# FPGA_0.net
KiCad netlist of a schematic drawn in Altium Designer
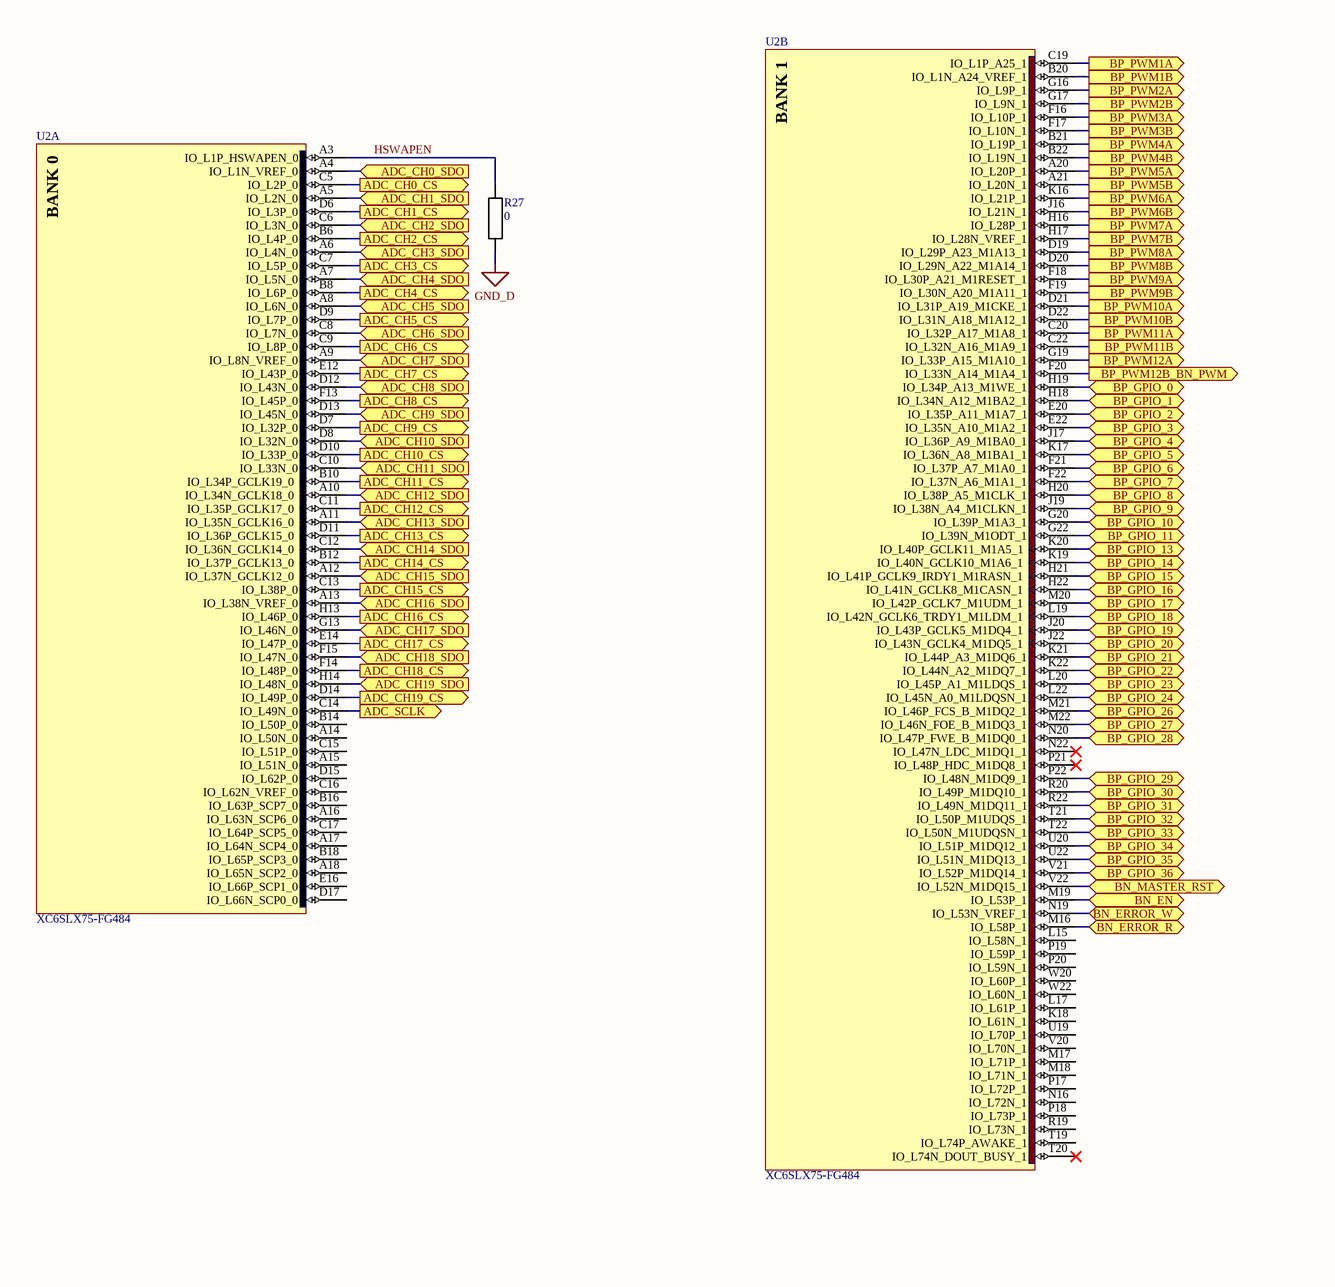
[diagram p0: FPGA_0.SchDoc, left]
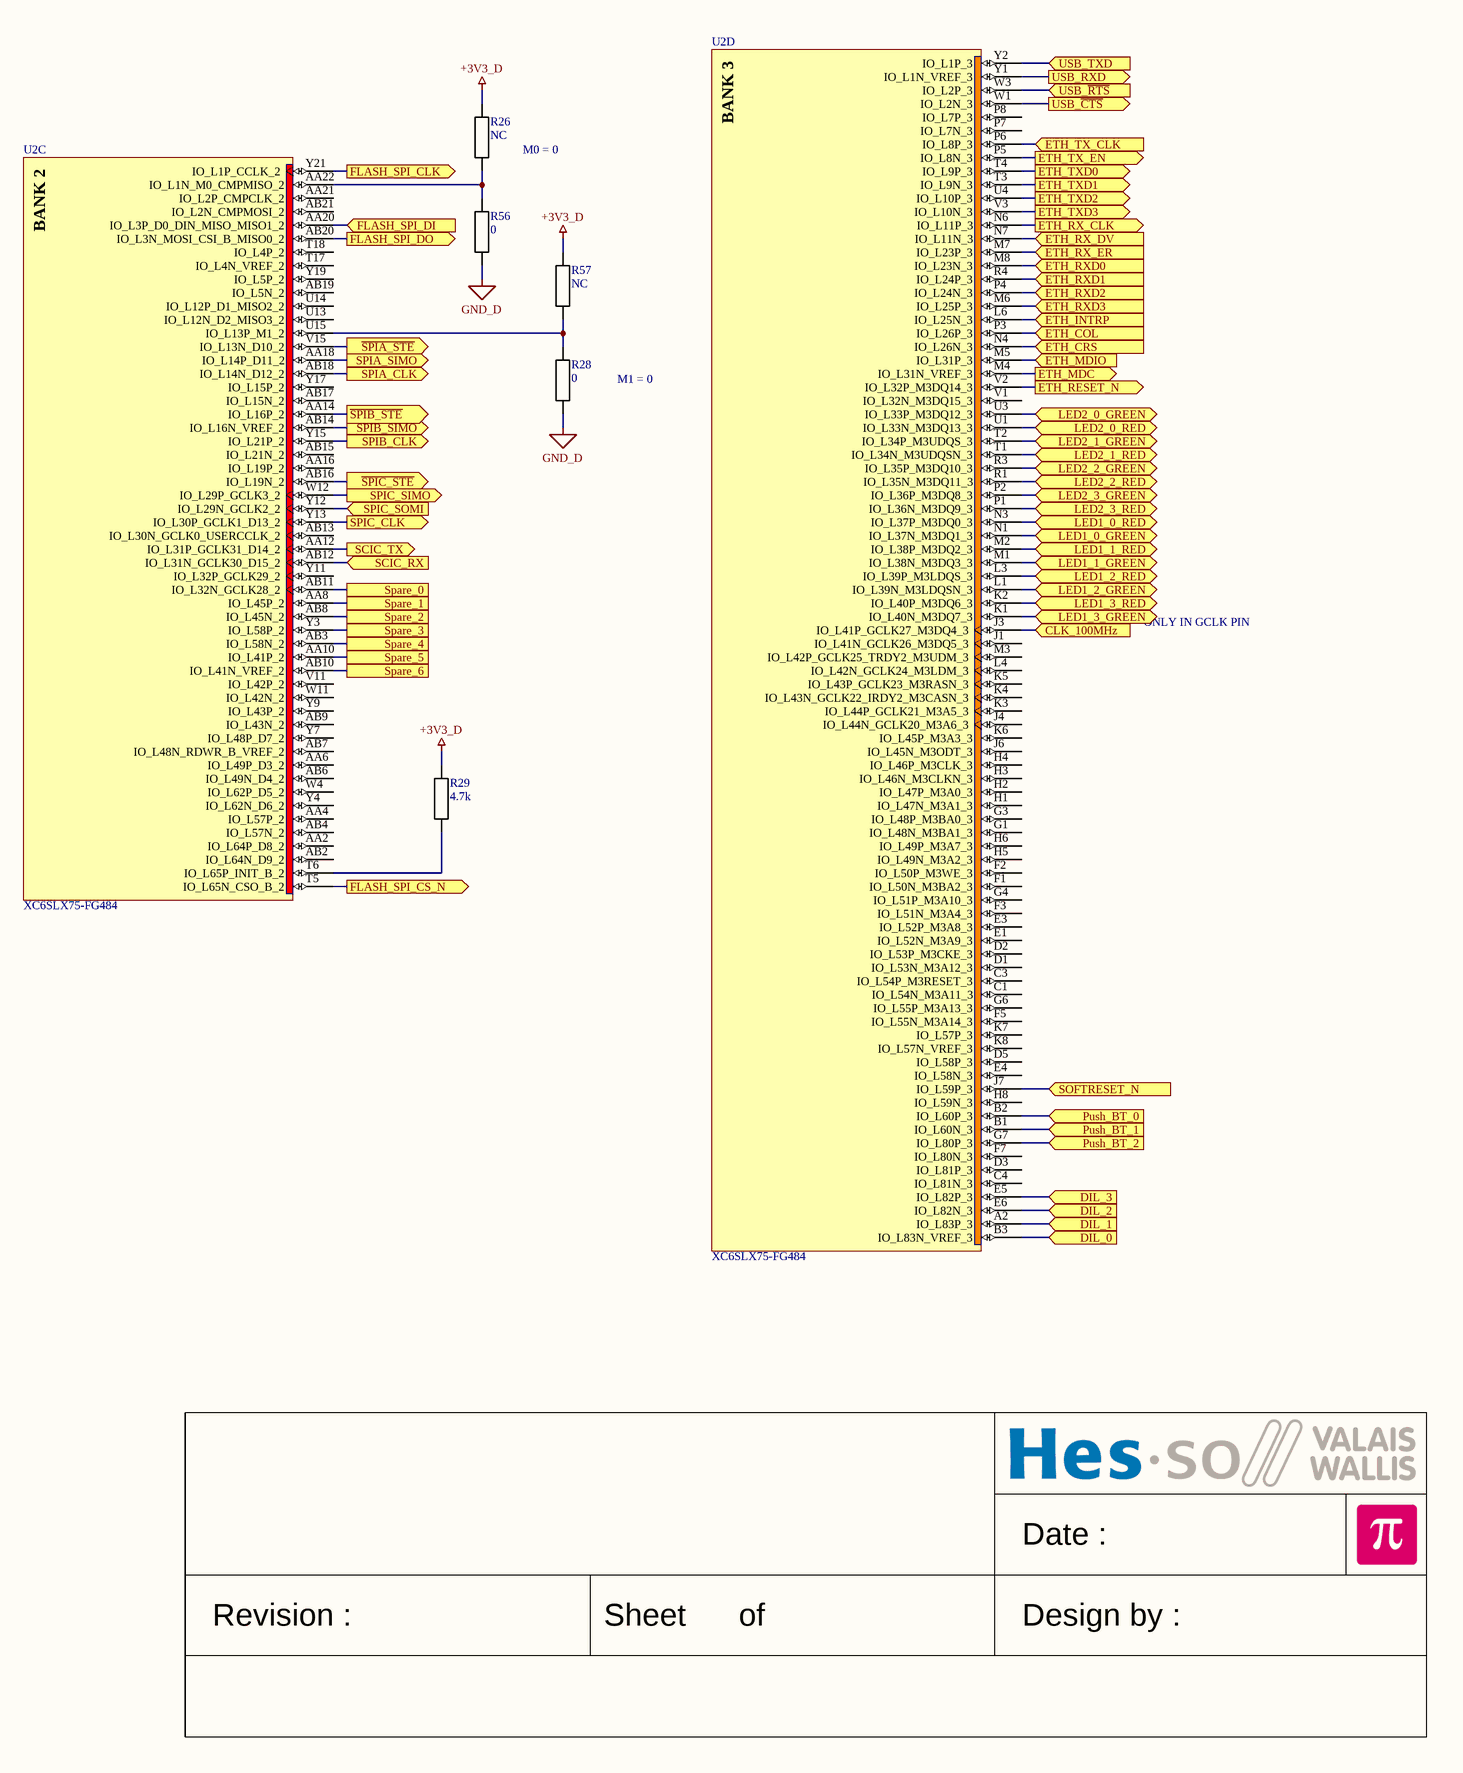
[diagram p1: FPGA_0.SchDoc, right]

(export (version "E")
  (design (tool "Eeschema 10.0.6"))
  (components
    (comp (ref "R26")
      (value "NC")
      (footprint "RESISTOR 2012 REFLOW")
      (description "Resistor 1% 50V 125mW 2012(0805)")
      (libsource (lib "Resistor") (part "Resistor"))
    )
    (comp (ref "R27")
      (value "0")
      (footprint "RESISTOR 2012 REFLOW")
      (description "Resistor 1% 50V 125mW 2012(0805)")
      (libsource (lib "Resistor") (part "Resistor"))
    )
    (comp (ref "R28")
      (value "0")
      (footprint "RESISTOR 2012 REFLOW")
      (description "Resistor 1% 50V 125mW 2012(0805)")
      (libsource (lib "Resistor") (part "Resistor"))
    )
    (comp (ref "R29")
      (value "4.7k")
      (footprint "RESISTOR 2012 REFLOW")
      (description "Resistor 1% 50V 125mW 2012(0805)")
      (libsource (lib "Resistor") (part "Resistor"))
    )
    (comp (ref "R56")
      (value "0")
      (footprint "RESISTOR 2012 REFLOW")
      (description "Resistor 1% 50V 125mW 2012(0805)")
      (libsource (lib "Resistor") (part "Resistor"))
    )
    (comp (ref "R57")
      (value "NC")
      (footprint "RESISTOR 2012 REFLOW")
      (description "Resistor 1% 50V 125mW 2012(0805)")
      (libsource (lib "Resistor") (part "Resistor"))
    )
    (comp (ref "U2")
      (value "XC6SLX75-FG484")
      (footprint "BGA484 P1.0 C23X23 H2.2")
      (description "Spartan-6 LXT 1.2V FPGA, 268 User I/Os, 484-Ball Fine-Pitch BGA (1.0mm Pitch)")
      (libsource (lib "Processor") (part "XC6SLX75-FG484"))
    )
  )
  (nets
    (net (code "1") (name "+3V3_D") (class "Default")
      (node (ref "R26") (pin "2") (pinfunction "2_2") (pintype "passive"))
      (node (ref "R29") (pin "2") (pinfunction "2_2") (pintype "passive"))
      (node (ref "R57") (pin "2") (pinfunction "2_2") (pintype "passive"))
    )
    (net (code "2") (name "/ADC_CH0_CS") (class "Default")
      (node (ref "U2") (pin "C5") (pinfunction "IO_L2P_0_C5") (pintype "bidirectional"))
    )
    (net (code "3") (name "/ADC_CH0_SDO") (class "Default")
      (node (ref "U2") (pin "A4") (pinfunction "IO_L1N_VREF_0_A4") (pintype "bidirectional"))
    )
    (net (code "4") (name "/ADC_CH1_CS") (class "Default")
      (node (ref "U2") (pin "D6") (pinfunction "IO_L3P_0_D6") (pintype "bidirectional"))
    )
    (net (code "5") (name "/ADC_CH1_SDO") (class "Default")
      (node (ref "U2") (pin "A5") (pinfunction "IO_L2N_0_A5") (pintype "bidirectional"))
    )
    (net (code "6") (name "/ADC_CH2_CS") (class "Default")
      (node (ref "U2") (pin "B6") (pinfunction "IO_L4P_0_B6") (pintype "bidirectional"))
    )
    (net (code "7") (name "/ADC_CH2_SDO") (class "Default")
      (node (ref "U2") (pin "C6") (pinfunction "IO_L3N_0_C6") (pintype "bidirectional"))
    )
    (net (code "8") (name "/ADC_CH3_CS") (class "Default")
      (node (ref "U2") (pin "C7") (pinfunction "IO_L5P_0_C7") (pintype "bidirectional"))
    )
    (net (code "9") (name "/ADC_CH3_SDO") (class "Default")
      (node (ref "U2") (pin "A6") (pinfunction "IO_L4N_0_A6") (pintype "bidirectional"))
    )
    (net (code "10") (name "/ADC_CH4_CS") (class "Default")
      (node (ref "U2") (pin "B8") (pinfunction "IO_L6P_0_B8") (pintype "bidirectional"))
    )
    (net (code "11") (name "/ADC_CH4_SDO") (class "Default")
      (node (ref "U2") (pin "A7") (pinfunction "IO_L5N_0_A7") (pintype "bidirectional"))
    )
    (net (code "12") (name "/ADC_CH5_CS") (class "Default")
      (node (ref "U2") (pin "D9") (pinfunction "IO_L7P_0_D9") (pintype "bidirectional"))
    )
    (net (code "13") (name "/ADC_CH5_SDO") (class "Default")
      (node (ref "U2") (pin "A8") (pinfunction "IO_L6N_0_A8") (pintype "bidirectional"))
    )
    (net (code "14") (name "/ADC_CH6_CS") (class "Default")
      (node (ref "U2") (pin "C9") (pinfunction "IO_L8P_0_C9") (pintype "bidirectional"))
    )
    (net (code "15") (name "/ADC_CH6_SDO") (class "Default")
      (node (ref "U2") (pin "C8") (pinfunction "IO_L7N_0_C8") (pintype "bidirectional"))
    )
    (net (code "16") (name "/ADC_CH7_CS") (class "Default")
      (node (ref "U2") (pin "E12") (pinfunction "IO_L43P_0_E12") (pintype "bidirectional"))
    )
    (net (code "17") (name "/ADC_CH7_SDO") (class "Default")
      (node (ref "U2") (pin "A9") (pinfunction "IO_L8N_VREF_0_A9") (pintype "bidirectional"))
    )
    (net (code "18") (name "/ADC_CH8_CS") (class "Default")
      (node (ref "U2") (pin "F13") (pinfunction "IO_L45P_0_F13") (pintype "bidirectional"))
    )
    (net (code "19") (name "/ADC_CH8_SDO") (class "Default")
      (node (ref "U2") (pin "D12") (pinfunction "IO_L43N_0_D12") (pintype "bidirectional"))
    )
    (net (code "20") (name "/ADC_CH9_CS") (class "Default")
      (node (ref "U2") (pin "D7") (pinfunction "IO_L32P_0_D7") (pintype "bidirectional"))
    )
    (net (code "21") (name "/ADC_CH9_SDO") (class "Default")
      (node (ref "U2") (pin "D13") (pinfunction "IO_L45N_0_D13") (pintype "bidirectional"))
    )
    (net (code "22") (name "/ADC_CH10_CS") (class "Default")
      (node (ref "U2") (pin "D10") (pinfunction "IO_L33P_0_D10") (pintype "bidirectional"))
    )
    (net (code "23") (name "/ADC_CH10_SDO") (class "Default")
      (node (ref "U2") (pin "D8") (pinfunction "IO_L32N_0_D8") (pintype "bidirectional"))
    )
    (net (code "24") (name "/ADC_CH11_CS") (class "Default")
      (node (ref "U2") (pin "B10") (pinfunction "IO_L34P_GCLK19_0_B10") (pintype "bidirectional"))
    )
    (net (code "25") (name "/ADC_CH11_SDO") (class "Default")
      (node (ref "U2") (pin "C10") (pinfunction "IO_L33N_0_C10") (pintype "bidirectional"))
    )
    (net (code "26") (name "/ADC_CH12_CS") (class "Default")
      (node (ref "U2") (pin "C11") (pinfunction "IO_L35P_GCLK17_0_C11") (pintype "bidirectional"))
    )
    (net (code "27") (name "/ADC_CH12_SDO") (class "Default")
      (node (ref "U2") (pin "A10") (pinfunction "IO_L34N_GCLK18_0_A10") (pintype "bidirectional"))
    )
    (net (code "28") (name "/ADC_CH13_CS") (class "Default")
      (node (ref "U2") (pin "D11") (pinfunction "IO_L36P_GCLK15_0_D11") (pintype "bidirectional"))
    )
    (net (code "29") (name "/ADC_CH13_SDO") (class "Default")
      (node (ref "U2") (pin "A11") (pinfunction "IO_L35N_GCLK16_0_A11") (pintype "bidirectional"))
    )
    (net (code "30") (name "/ADC_CH14_CS") (class "Default")
      (node (ref "U2") (pin "B12") (pinfunction "IO_L37P_GCLK13_0_B12") (pintype "bidirectional"))
    )
    (net (code "31") (name "/ADC_CH14_SDO") (class "Default")
      (node (ref "U2") (pin "C12") (pinfunction "IO_L36N_GCLK14_0_C12") (pintype "bidirectional"))
    )
    (net (code "32") (name "/ADC_CH15_CS") (class "Default")
      (node (ref "U2") (pin "C13") (pinfunction "IO_L38P_0_C13") (pintype "bidirectional"))
    )
    (net (code "33") (name "/ADC_CH15_SDO") (class "Default")
      (node (ref "U2") (pin "A12") (pinfunction "IO_L37N_GCLK12_0_A12") (pintype "bidirectional"))
    )
    (net (code "34") (name "/ADC_CH16_CS") (class "Default")
      (node (ref "U2") (pin "H13") (pinfunction "IO_L46P_0_H13") (pintype "bidirectional"))
    )
    (net (code "35") (name "/ADC_CH16_SDO") (class "Default")
      (node (ref "U2") (pin "A13") (pinfunction "IO_L38N_VREF_0_A13") (pintype "bidirectional"))
    )
    (net (code "36") (name "/ADC_CH17_CS") (class "Default")
      (node (ref "U2") (pin "E14") (pinfunction "IO_L47P_0_E14") (pintype "bidirectional"))
    )
    (net (code "37") (name "/ADC_CH17_SDO") (class "Default")
      (node (ref "U2") (pin "G13") (pinfunction "IO_L46N_0_G13") (pintype "bidirectional"))
    )
    (net (code "38") (name "/ADC_CH18_CS") (class "Default")
      (node (ref "U2") (pin "F14") (pinfunction "IO_L48P_0_F14") (pintype "bidirectional"))
    )
    (net (code "39") (name "/ADC_CH18_SDO") (class "Default")
      (node (ref "U2") (pin "F15") (pinfunction "IO_L47N_0_F15") (pintype "bidirectional"))
    )
    (net (code "40") (name "/ADC_CH19_CS") (class "Default")
      (node (ref "U2") (pin "D14") (pinfunction "IO_L49P_0_D14") (pintype "bidirectional"))
    )
    (net (code "41") (name "/ADC_CH19_SDO") (class "Default")
      (node (ref "U2") (pin "H14") (pinfunction "IO_L48N_0_H14") (pintype "bidirectional"))
    )
    (net (code "42") (name "/ADC_SCLK") (class "Default")
      (node (ref "U2") (pin "C14") (pinfunction "IO_L49N_0_C14") (pintype "bidirectional"))
    )
    (net (code "43") (name "/BN_EN") (class "Default")
      (node (ref "U2") (pin "M19") (pinfunction "IO_L53P_1_M19") (pintype "bidirectional"))
    )
    (net (code "44") (name "/BN_ERROR_R") (class "Default")
      (node (ref "U2") (pin "M16") (pinfunction "IO_L58P_1_M16") (pintype "bidirectional"))
    )
    (net (code "45") (name "/BN_ERROR_W") (class "Default")
      (node (ref "U2") (pin "N19") (pinfunction "IO_L53N_VREF_1_N19") (pintype "bidirectional"))
    )
    (net (code "46") (name "/BN_MASTER_RST") (class "Default")
      (node (ref "U2") (pin "V22") (pinfunction "IO_L52N_M1DQ15_1_V22") (pintype "bidirectional"))
    )
    (net (code "47") (name "/BP_GPIO_0") (class "Default")
      (node (ref "U2") (pin "H19") (pinfunction "IO_L34P_A13_M1WE_1_H19") (pintype "bidirectional"))
    )
    (net (code "48") (name "/BP_GPIO_1") (class "Default")
      (node (ref "U2") (pin "H18") (pinfunction "IO_L34N_A12_M1BA2_1_H18") (pintype "bidirectional"))
    )
    (net (code "49") (name "/BP_GPIO_2") (class "Default")
      (node (ref "U2") (pin "E20") (pinfunction "IO_L35P_A11_M1A7_1_E20") (pintype "bidirectional"))
    )
    (net (code "50") (name "/BP_GPIO_3") (class "Default")
      (node (ref "U2") (pin "E22") (pinfunction "IO_L35N_A10_M1A2_1_E22") (pintype "bidirectional"))
    )
    (net (code "51") (name "/BP_GPIO_4") (class "Default")
      (node (ref "U2") (pin "J17") (pinfunction "IO_L36P_A9_M1BA0_1_J17") (pintype "bidirectional"))
    )
    (net (code "52") (name "/BP_GPIO_5") (class "Default")
      (node (ref "U2") (pin "K17") (pinfunction "IO_L36N_A8_M1BA1_1_K17") (pintype "bidirectional"))
    )
    (net (code "53") (name "/BP_GPIO_6") (class "Default")
      (node (ref "U2") (pin "F21") (pinfunction "IO_L37P_A7_M1A0_1_F21") (pintype "bidirectional"))
    )
    (net (code "54") (name "/BP_GPIO_7") (class "Default")
      (node (ref "U2") (pin "F22") (pinfunction "IO_L37N_A6_M1A1_1_F22") (pintype "bidirectional"))
    )
    (net (code "55") (name "/BP_GPIO_8") (class "Default")
      (node (ref "U2") (pin "H20") (pinfunction "IO_L38P_A5_M1CLK_1_H20") (pintype "bidirectional"))
    )
    (net (code "56") (name "/BP_GPIO_9") (class "Default")
      (node (ref "U2") (pin "J19") (pinfunction "IO_L38N_A4_M1CLKN_1_J19") (pintype "bidirectional"))
    )
    (net (code "57") (name "/BP_GPIO_10") (class "Default")
      (node (ref "U2") (pin "G20") (pinfunction "IO_L39P_M1A3_1_G20") (pintype "bidirectional"))
    )
    (net (code "58") (name "/BP_GPIO_11") (class "Default")
      (node (ref "U2") (pin "G22") (pinfunction "IO_L39N_M1ODT_1_G22") (pintype "bidirectional"))
    )
    (net (code "59") (name "/BP_GPIO_13") (class "Default")
      (node (ref "U2") (pin "K20") (pinfunction "IO_L40P_GCLK11_M1A5_1_K20") (pintype "bidirectional"))
    )
    (net (code "60") (name "/BP_GPIO_14") (class "Default")
      (node (ref "U2") (pin "K19") (pinfunction "IO_L40N_GCLK10_M1A6_1_K19") (pintype "bidirectional"))
    )
    (net (code "61") (name "/BP_GPIO_15") (class "Default")
      (node (ref "U2") (pin "H21") (pinfunction "IO_L41P_GCLK9_IRDY1_M1RASN_1_H21") (pintype "bidirectional"))
    )
    (net (code "62") (name "/BP_GPIO_16") (class "Default")
      (node (ref "U2") (pin "H22") (pinfunction "IO_L41N_GCLK8_M1CASN_1_H22") (pintype "bidirectional"))
    )
    (net (code "63") (name "/BP_GPIO_17") (class "Default")
      (node (ref "U2") (pin "M20") (pinfunction "IO_L42P_GCLK7_M1UDM_1_M20") (pintype "bidirectional"))
    )
    (net (code "64") (name "/BP_GPIO_18") (class "Default")
      (node (ref "U2") (pin "L19") (pinfunction "IO_L42N_GCLK6_TRDY1_M1LDM_1_L19") (pintype "bidirectional"))
    )
    (net (code "65") (name "/BP_GPIO_19") (class "Default")
      (node (ref "U2") (pin "J20") (pinfunction "IO_L43P_GCLK5_M1DQ4_1_J20") (pintype "bidirectional"))
    )
    (net (code "66") (name "/BP_GPIO_20") (class "Default")
      (node (ref "U2") (pin "J22") (pinfunction "IO_L43N_GCLK4_M1DQ5_1_J22") (pintype "bidirectional"))
    )
    (net (code "67") (name "/BP_GPIO_21") (class "Default")
      (node (ref "U2") (pin "K21") (pinfunction "IO_L44P_A3_M1DQ6_1_K21") (pintype "bidirectional"))
    )
    (net (code "68") (name "/BP_GPIO_22") (class "Default")
      (node (ref "U2") (pin "K22") (pinfunction "IO_L44N_A2_M1DQ7_1_K22") (pintype "bidirectional"))
    )
    (net (code "69") (name "/BP_GPIO_23") (class "Default")
      (node (ref "U2") (pin "L20") (pinfunction "IO_L45P_A1_M1LDQS_1_L20") (pintype "bidirectional"))
    )
    (net (code "70") (name "/BP_GPIO_24") (class "Default")
      (node (ref "U2") (pin "L22") (pinfunction "IO_L45N_A0_M1LDQSN_1_L22") (pintype "bidirectional"))
    )
    (net (code "71") (name "/BP_GPIO_26") (class "Default")
      (node (ref "U2") (pin "M21") (pinfunction "IO_L46P_FCS_B_M1DQ2_1_M21") (pintype "bidirectional"))
    )
    (net (code "72") (name "/BP_GPIO_27") (class "Default")
      (node (ref "U2") (pin "M22") (pinfunction "IO_L46N_FOE_B_M1DQ3_1_M22") (pintype "bidirectional"))
    )
    (net (code "73") (name "/BP_GPIO_28") (class "Default")
      (node (ref "U2") (pin "N20") (pinfunction "IO_L47P_FWE_B_M1DQ0_1_N20") (pintype "bidirectional"))
    )
    (net (code "74") (name "/BP_GPIO_29") (class "Default")
      (node (ref "U2") (pin "P22") (pinfunction "IO_L48N_M1DQ9_1_P22") (pintype "bidirectional"))
    )
    (net (code "75") (name "/BP_GPIO_30") (class "Default")
      (node (ref "U2") (pin "R20") (pinfunction "IO_L49P_M1DQ10_1_R20") (pintype "bidirectional"))
    )
    (net (code "76") (name "/BP_GPIO_31") (class "Default")
      (node (ref "U2") (pin "R22") (pinfunction "IO_L49N_M1DQ11_1_R22") (pintype "bidirectional"))
    )
    (net (code "77") (name "/BP_GPIO_32") (class "Default")
      (node (ref "U2") (pin "T21") (pinfunction "IO_L50P_M1UDQS_1_T21") (pintype "bidirectional"))
    )
    (net (code "78") (name "/BP_GPIO_33") (class "Default")
      (node (ref "U2") (pin "T22") (pinfunction "IO_L50N_M1UDQSN_1_T22") (pintype "bidirectional"))
    )
    (net (code "79") (name "/BP_GPIO_34") (class "Default")
      (node (ref "U2") (pin "U20") (pinfunction "IO_L51P_M1DQ12_1_U20") (pintype "bidirectional"))
    )
    (net (code "80") (name "/BP_GPIO_35") (class "Default")
      (node (ref "U2") (pin "U22") (pinfunction "IO_L51N_M1DQ13_1_U22") (pintype "bidirectional"))
    )
    (net (code "81") (name "/BP_GPIO_36") (class "Default")
      (node (ref "U2") (pin "V21") (pinfunction "IO_L52P_M1DQ14_1_V21") (pintype "bidirectional"))
    )
    (net (code "82") (name "/BP_PWM1A") (class "Default")
      (node (ref "U2") (pin "C19") (pinfunction "IO_L1P_A25_1_C19") (pintype "bidirectional"))
    )
    (net (code "83") (name "/BP_PWM1B") (class "Default")
      (node (ref "U2") (pin "B20") (pinfunction "IO_L1N_A24_VREF_1_B20") (pintype "bidirectional"))
    )
    (net (code "84") (name "/BP_PWM2A") (class "Default")
      (node (ref "U2") (pin "G16") (pinfunction "IO_L9P_1_G16") (pintype "bidirectional"))
    )
    (net (code "85") (name "/BP_PWM2B") (class "Default")
      (node (ref "U2") (pin "G17") (pinfunction "IO_L9N_1_G17") (pintype "bidirectional"))
    )
    (net (code "86") (name "/BP_PWM3A") (class "Default")
      (node (ref "U2") (pin "F16") (pinfunction "IO_L10P_1_F16") (pintype "bidirectional"))
    )
    (net (code "87") (name "/BP_PWM3B") (class "Default")
      (node (ref "U2") (pin "F17") (pinfunction "IO_L10N_1_F17") (pintype "bidirectional"))
    )
    (net (code "88") (name "/BP_PWM4A") (class "Default")
      (node (ref "U2") (pin "B21") (pinfunction "IO_L19P_1_B21") (pintype "bidirectional"))
    )
    (net (code "89") (name "/BP_PWM4B") (class "Default")
      (node (ref "U2") (pin "B22") (pinfunction "IO_L19N_1_B22") (pintype "bidirectional"))
    )
    (net (code "90") (name "/BP_PWM5A") (class "Default")
      (node (ref "U2") (pin "A20") (pinfunction "IO_L20P_1_A20") (pintype "bidirectional"))
    )
    (net (code "91") (name "/BP_PWM5B") (class "Default")
      (node (ref "U2") (pin "A21") (pinfunction "IO_L20N_1_A21") (pintype "bidirectional"))
    )
    (net (code "92") (name "/BP_PWM6A") (class "Default")
      (node (ref "U2") (pin "K16") (pinfunction "IO_L21P_1_K16") (pintype "bidirectional"))
    )
    (net (code "93") (name "/BP_PWM6B") (class "Default")
      (node (ref "U2") (pin "J16") (pinfunction "IO_L21N_1_J16") (pintype "bidirectional"))
    )
    (net (code "94") (name "/BP_PWM7A") (class "Default")
      (node (ref "U2") (pin "H16") (pinfunction "IO_L28P_1_H16") (pintype "bidirectional"))
    )
    (net (code "95") (name "/BP_PWM7B") (class "Default")
      (node (ref "U2") (pin "H17") (pinfunction "IO_L28N_VREF_1_H17") (pintype "bidirectional"))
    )
    (net (code "96") (name "/BP_PWM8A") (class "Default")
      (node (ref "U2") (pin "D19") (pinfunction "IO_L29P_A23_M1A13_1_D19") (pintype "bidirectional"))
    )
    (net (code "97") (name "/BP_PWM8B") (class "Default")
      (node (ref "U2") (pin "D20") (pinfunction "IO_L29N_A22_M1A14_1_D20") (pintype "bidirectional"))
    )
    (net (code "98") (name "/BP_PWM9A") (class "Default")
      (node (ref "U2") (pin "F18") (pinfunction "IO_L30P_A21_M1RESET_1_F18") (pintype "bidirectional"))
    )
    (net (code "99") (name "/BP_PWM9B") (class "Default")
      (node (ref "U2") (pin "F19") (pinfunction "IO_L30N_A20_M1A11_1_F19") (pintype "bidirectional"))
    )
    (net (code "100") (name "/BP_PWM10A") (class "Default")
      (node (ref "U2") (pin "D21") (pinfunction "IO_L31P_A19_M1CKE_1_D21") (pintype "bidirectional"))
    )
    (net (code "101") (name "/BP_PWM10B") (class "Default")
      (node (ref "U2") (pin "D22") (pinfunction "IO_L31N_A18_M1A12_1_D22") (pintype "bidirectional"))
    )
    (net (code "102") (name "/BP_PWM11A") (class "Default")
      (node (ref "U2") (pin "C20") (pinfunction "IO_L32P_A17_M1A8_1_C20") (pintype "bidirectional"))
    )
    (net (code "103") (name "/BP_PWM11B") (class "Default")
      (node (ref "U2") (pin "C22") (pinfunction "IO_L32N_A16_M1A9_1_C22") (pintype "bidirectional"))
    )
    (net (code "104") (name "/BP_PWM12A") (class "Default")
      (node (ref "U2") (pin "G19") (pinfunction "IO_L33P_A15_M1A10_1_G19") (pintype "bidirectional"))
    )
    (net (code "105") (name "/BP_PWM12B_BN_PWM") (class "Default")
      (node (ref "U2") (pin "F20") (pinfunction "IO_L33N_A14_M1A4_1_F20") (pintype "bidirectional"))
    )
    (net (code "106") (name "/CLK_100MHz") (class "Default")
      (node (ref "U2") (pin "J3") (pinfunction "IO_L41P_GCLK27_M3DQ4_3_J3") (pintype "bidirectional"))
    )
    (net (code "107") (name "/DIL_0") (class "Default")
      (node (ref "U2") (pin "B3") (pinfunction "IO_L83N_VREF_3_B3") (pintype "bidirectional"))
    )
    (net (code "108") (name "/DIL_1") (class "Default")
      (node (ref "U2") (pin "A2") (pinfunction "IO_L83P_3_A2") (pintype "bidirectional"))
    )
    (net (code "109") (name "/DIL_2") (class "Default")
      (node (ref "U2") (pin "E6") (pinfunction "IO_L82N_3_E6") (pintype "bidirectional"))
    )
    (net (code "110") (name "/DIL_3") (class "Default")
      (node (ref "U2") (pin "E5") (pinfunction "IO_L82P_3_E5") (pintype "bidirectional"))
    )
    (net (code "111") (name "/ETH_COL") (class "Default")
      (node (ref "U2") (pin "P3") (pinfunction "IO_L26P_3_P3") (pintype "bidirectional"))
    )
    (net (code "112") (name "/ETH_CRS") (class "Default")
      (node (ref "U2") (pin "N4") (pinfunction "IO_L26N_3_N4") (pintype "bidirectional"))
    )
    (net (code "113") (name "/ETH_INTRP") (class "Default")
      (node (ref "U2") (pin "L6") (pinfunction "IO_L25N_3_L6") (pintype "bidirectional"))
    )
    (net (code "114") (name "/ETH_MDC") (class "Default")
      (node (ref "U2") (pin "M4") (pinfunction "IO_L31N_VREF_3_M4") (pintype "bidirectional"))
    )
    (net (code "115") (name "/ETH_MDIO") (class "Default")
      (node (ref "U2") (pin "M5") (pinfunction "IO_L31P_3_M5") (pintype "bidirectional"))
    )
    (net (code "116") (name "/ETH_RESET_N") (class "Default")
      (node (ref "U2") (pin "V2") (pinfunction "IO_L32P_M3DQ14_3_V2") (pintype "bidirectional"))
    )
    (net (code "117") (name "/ETH_RXD0") (class "Default")
      (node (ref "U2") (pin "M8") (pinfunction "IO_L23N_3_M8") (pintype "bidirectional"))
    )
    (net (code "118") (name "/ETH_RXD1") (class "Default")
      (node (ref "U2") (pin "R4") (pinfunction "IO_L24P_3_R4") (pintype "bidirectional"))
    )
    (net (code "119") (name "/ETH_RXD2") (class "Default")
      (node (ref "U2") (pin "P4") (pinfunction "IO_L24N_3_P4") (pintype "bidirectional"))
    )
    (net (code "120") (name "/ETH_RXD3") (class "Default")
      (node (ref "U2") (pin "M6") (pinfunction "IO_L25P_3_M6") (pintype "bidirectional"))
    )
    (net (code "121") (name "/ETH_RX_CLK") (class "Default")
      (node (ref "U2") (pin "N6") (pinfunction "IO_L11P_3_N6") (pintype "bidirectional"))
    )
    (net (code "122") (name "/ETH_RX_DV") (class "Default")
      (node (ref "U2") (pin "N7") (pinfunction "IO_L11N_3_N7") (pintype "bidirectional"))
    )
    (net (code "123") (name "/ETH_RX_ER") (class "Default")
      (node (ref "U2") (pin "M7") (pinfunction "IO_L23P_3_M7") (pintype "bidirectional"))
    )
    (net (code "124") (name "/ETH_TXD0") (class "Default")
      (node (ref "U2") (pin "T4") (pinfunction "IO_L9P_3_T4") (pintype "bidirectional"))
    )
    (net (code "125") (name "/ETH_TXD1") (class "Default")
      (node (ref "U2") (pin "T3") (pinfunction "IO_L9N_3_T3") (pintype "bidirectional"))
    )
    (net (code "126") (name "/ETH_TXD2") (class "Default")
      (node (ref "U2") (pin "U4") (pinfunction "IO_L10P_3_U4") (pintype "bidirectional"))
    )
    (net (code "127") (name "/ETH_TXD3") (class "Default")
      (node (ref "U2") (pin "V3") (pinfunction "IO_L10N_3_V3") (pintype "bidirectional"))
    )
    (net (code "128") (name "/ETH_TX_CLK") (class "Default")
      (node (ref "U2") (pin "P6") (pinfunction "IO_L8P_3_P6") (pintype "bidirectional"))
    )
    (net (code "129") (name "/ETH_TX_EN") (class "Default")
      (node (ref "U2") (pin "P5") (pinfunction "IO_L8N_3_P5") (pintype "bidirectional"))
    )
    (net (code "130") (name "/FLASH_SPI_CLK") (class "Default")
      (node (ref "U2") (pin "Y21") (pinfunction "IO_L1P_CCLK_2_Y21") (pintype "bidirectional"))
    )
    (net (code "131") (name "/FLASH_SPI_CS_N") (class "Default")
      (node (ref "U2") (pin "T5") (pinfunction "IO_L65N_CSO_B_2_T5") (pintype "bidirectional"))
    )
    (net (code "132") (name "/FLASH_SPI_DI") (class "Default")
      (node (ref "U2") (pin "AA20") (pinfunction "IO_L3P_D0_DIN_MISO_MISO1_2_AA20") (pintype "bidirectional"))
    )
    (net (code "133") (name "/FLASH_SPI_DO") (class "Default")
      (node (ref "U2") (pin "AB20") (pinfunction "IO_L3N_MOSI_CSI_B_MISO0_2_AB20") (pintype "bidirectional"))
    )
    (net (code "134") (name "/HSWAPEN") (class "Default")
      (node (ref "R27") (pin "2") (pinfunction "2_2") (pintype "passive"))
      (node (ref "U2") (pin "A3") (pinfunction "IO_L1P_HSWAPEN_0_A3") (pintype "bidirectional"))
    )
    (net (code "135") (name "/LED1_0_GREEN") (class "Default")
      (node (ref "U2") (pin "N1") (pinfunction "IO_L37N_M3DQ1_3_N1") (pintype "bidirectional"))
    )
    (net (code "136") (name "/LED1_0_RED") (class "Default")
      (node (ref "U2") (pin "N3") (pinfunction "IO_L37P_M3DQ0_3_N3") (pintype "bidirectional"))
    )
    (net (code "137") (name "/LED1_1_GREEN") (class "Default")
      (node (ref "U2") (pin "M1") (pinfunction "IO_L38N_M3DQ3_3_M1") (pintype "bidirectional"))
    )
    (net (code "138") (name "/LED1_1_RED") (class "Default")
      (node (ref "U2") (pin "M2") (pinfunction "IO_L38P_M3DQ2_3_M2") (pintype "bidirectional"))
    )
    (net (code "139") (name "/LED1_2_GREEN") (class "Default")
      (node (ref "U2") (pin "L1") (pinfunction "IO_L39N_M3LDQSN_3_L1") (pintype "bidirectional"))
    )
    (net (code "140") (name "/LED1_2_RED") (class "Default")
      (node (ref "U2") (pin "L3") (pinfunction "IO_L39P_M3LDQS_3_L3") (pintype "bidirectional"))
    )
    (net (code "141") (name "/LED1_3_GREEN") (class "Default")
      (node (ref "U2") (pin "K1") (pinfunction "IO_L40N_M3DQ7_3_K1") (pintype "bidirectional"))
    )
    (net (code "142") (name "/LED1_3_RED") (class "Default")
      (node (ref "U2") (pin "K2") (pinfunction "IO_L40P_M3DQ6_3_K2") (pintype "bidirectional"))
    )
    (net (code "143") (name "/LED2_0_GREEN") (class "Default")
      (node (ref "U2") (pin "U3") (pinfunction "IO_L33P_M3DQ12_3_U3") (pintype "bidirectional"))
    )
    (net (code "144") (name "/LED2_0_RED") (class "Default")
      (node (ref "U2") (pin "U1") (pinfunction "IO_L33N_M3DQ13_3_U1") (pintype "bidirectional"))
    )
    (net (code "145") (name "/LED2_1_GREEN") (class "Default")
      (node (ref "U2") (pin "T2") (pinfunction "IO_L34P_M3UDQS_3_T2") (pintype "bidirectional"))
    )
    (net (code "146") (name "/LED2_1_RED") (class "Default")
      (node (ref "U2") (pin "T1") (pinfunction "IO_L34N_M3UDQSN_3_T1") (pintype "bidirectional"))
    )
    (net (code "147") (name "/LED2_2_GREEN") (class "Default")
      (node (ref "U2") (pin "R3") (pinfunction "IO_L35P_M3DQ10_3_R3") (pintype "bidirectional"))
    )
    (net (code "148") (name "/LED2_2_RED") (class "Default")
      (node (ref "U2") (pin "R1") (pinfunction "IO_L35N_M3DQ11_3_R1") (pintype "bidirectional"))
    )
    (net (code "149") (name "/LED2_3_GREEN") (class "Default")
      (node (ref "U2") (pin "P2") (pinfunction "IO_L36P_M3DQ8_3_P2") (pintype "bidirectional"))
    )
    (net (code "150") (name "/LED2_3_RED") (class "Default")
      (node (ref "U2") (pin "P1") (pinfunction "IO_L36N_M3DQ9_3_P1") (pintype "bidirectional"))
    )
    (net (code "151") (name "/Push_BT_0") (class "Default")
      (node (ref "U2") (pin "B2") (pinfunction "IO_L60P_3_B2") (pintype "bidirectional"))
    )
    (net (code "152") (name "/Push_BT_1") (class "Default")
      (node (ref "U2") (pin "B1") (pinfunction "IO_L60N_3_B1") (pintype "bidirectional"))
    )
    (net (code "153") (name "/Push_BT_2") (class "Default")
      (node (ref "U2") (pin "G7") (pinfunction "IO_L80P_3_G7") (pintype "bidirectional"))
    )
    (net (code "154") (name "/SCIC_RX") (class "Default")
      (node (ref "U2") (pin "AB12") (pinfunction "IO_L31N_GCLK30_D15_2_AB12") (pintype "bidirectional"))
    )
    (net (code "155") (name "/SCIC_TX") (class "Default")
      (node (ref "U2") (pin "AA12") (pinfunction "IO_L31P_GCLK31_D14_2_AA12") (pintype "bidirectional"))
    )
    (net (code "156") (name "/SOFTRESET_N") (class "Default")
      (node (ref "U2") (pin "J7") (pinfunction "IO_L59P_3_J7") (pintype "bidirectional"))
    )
    (net (code "157") (name "/SPIA_CLK") (class "Default")
      (node (ref "U2") (pin "AB18") (pinfunction "IO_L14N_D12_2_AB18") (pintype "bidirectional"))
    )
    (net (code "158") (name "/SPIA_SIMO") (class "Default")
      (node (ref "U2") (pin "AA18") (pinfunction "IO_L14P_D11_2_AA18") (pintype "bidirectional"))
    )
    (net (code "159") (name "/SPIB_CLK") (class "Default")
      (node (ref "U2") (pin "Y15") (pinfunction "IO_L21P_2_Y15") (pintype "bidirectional"))
    )
    (net (code "160") (name "/SPIB_SIMO") (class "Default")
      (node (ref "U2") (pin "AB14") (pinfunction "IO_L16N_VREF_2_AB14") (pintype "bidirectional"))
    )
    (net (code "161") (name "/SPIC_CLK") (class "Default")
      (node (ref "U2") (pin "Y13") (pinfunction "IO_L30P_GCLK1_D13_2_Y13") (pintype "bidirectional"))
    )
    (net (code "162") (name "/SPIC_SIMO") (class "Default")
      (node (ref "U2") (pin "W12") (pinfunction "IO_L29P_GCLK3_2_W12") (pintype "bidirectional"))
    )
    (net (code "163") (name "/SPIC_SOMI") (class "Default")
      (node (ref "U2") (pin "Y12") (pinfunction "IO_L29N_GCLK2_2_Y12") (pintype "bidirectional"))
    )
    (net (code "164") (name "/Spare_0") (class "Default")
      (node (ref "U2") (pin "AB11") (pinfunction "IO_L32N_GCLK28_2_AB11") (pintype "bidirectional"))
    )
    (net (code "165") (name "/Spare_1") (class "Default")
      (node (ref "U2") (pin "AA8") (pinfunction "IO_L45P_2_AA8") (pintype "bidirectional"))
    )
    (net (code "166") (name "/Spare_2") (class "Default")
      (node (ref "U2") (pin "AB8") (pinfunction "IO_L45N_2_AB8") (pintype "bidirectional"))
    )
    (net (code "167") (name "/Spare_3") (class "Default")
      (node (ref "U2") (pin "Y3") (pinfunction "IO_L58P_2_Y3") (pintype "bidirectional"))
    )
    (net (code "168") (name "/Spare_4") (class "Default")
      (node (ref "U2") (pin "AB3") (pinfunction "IO_L58N_2_AB3") (pintype "bidirectional"))
    )
    (net (code "169") (name "/Spare_5") (class "Default")
      (node (ref "U2") (pin "AA10") (pinfunction "IO_L41P_2_AA10") (pintype "bidirectional"))
    )
    (net (code "170") (name "/Spare_6") (class "Default")
      (node (ref "U2") (pin "AB10") (pinfunction "IO_L41N_VREF_2_AB10") (pintype "bidirectional"))
    )
    (net (code "171") (name "/USB_RXD") (class "Default")
      (node (ref "U2") (pin "Y1") (pinfunction "IO_L1N_VREF_3_Y1") (pintype "bidirectional"))
    )
    (net (code "172") (name "/USB_TXD") (class "Default")
      (node (ref "U2") (pin "Y2") (pinfunction "IO_L1P_3_Y2") (pintype "bidirectional"))
    )
    (net (code "173") (name "/USB_~{CTS}") (class "Default")
      (node (ref "U2") (pin "W1") (pinfunction "IO_L2N_3_W1") (pintype "bidirectional"))
    )
    (net (code "174") (name "/USB_~{RTS}") (class "Default")
      (node (ref "U2") (pin "W3") (pinfunction "IO_L2P_3_W3") (pintype "bidirectional"))
    )
    (net (code "175") (name "/~{SPIA_STE}") (class "Default")
      (node (ref "U2") (pin "V15") (pinfunction "IO_L13N_D10_2_V15") (pintype "bidirectional"))
    )
    (net (code "176") (name "/~{SPIB_STE}") (class "Default")
      (node (ref "U2") (pin "AA14") (pinfunction "IO_L16P_2_AA14") (pintype "bidirectional"))
    )
    (net (code "177") (name "/~{SPIC_STE}") (class "Default")
      (node (ref "U2") (pin "AB16") (pinfunction "IO_L19N_2_AB16") (pintype "bidirectional"))
    )
    (net (code "178") (name "GND_D") (class "Default")
      (node (ref "R27") (pin "1") (pinfunction "1_1") (pintype "passive"))
      (node (ref "R28") (pin "1") (pinfunction "1_1") (pintype "passive"))
      (node (ref "R56") (pin "1") (pinfunction "1_1") (pintype "passive"))
    )
    (net (code "179") (name "Net-(U2C-IO_L1N_M0_CMPMISO_2)") (class "Default")
      (node (ref "R26") (pin "1") (pinfunction "1_1") (pintype "passive"))
      (node (ref "R56") (pin "2") (pinfunction "2_2") (pintype "passive"))
      (node (ref "U2") (pin "AA22") (pinfunction "IO_L1N_M0_CMPMISO_2_AA22") (pintype "bidirectional"))
    )
    (net (code "180") (name "Net-(U2C-IO_L13P_M1_2)") (class "Default")
      (node (ref "R28") (pin "2") (pinfunction "2_2") (pintype "passive"))
      (node (ref "R57") (pin "1") (pinfunction "1_1") (pintype "passive"))
      (node (ref "U2") (pin "U15") (pinfunction "IO_L13P_M1_2_U15") (pintype "bidirectional"))
    )
    (net (code "181") (name "Net-(U2C-IO_L65P_INIT_B_2)") (class "Default")
      (node (ref "R29") (pin "1") (pinfunction "1_1") (pintype "passive"))
      (node (ref "U2") (pin "T6") (pinfunction "IO_L65P_INIT_B_2_T6") (pintype "bidirectional"))
    )
    (net (code "182") (name "unconnected-(U2A-IO_L50N_0-PadA14)") (class "Default")
      (node (ref "U2") (pin "A14") (pinfunction "IO_L50N_0_A14") (pintype "bidirectional"))
    )
    (net (code "183") (name "unconnected-(U2A-IO_L50P_0-PadB14)") (class "Default")
      (node (ref "U2") (pin "B14") (pinfunction "IO_L50P_0_B14") (pintype "bidirectional"))
    )
    (net (code "184") (name "unconnected-(U2A-IO_L51N_0-PadA15)") (class "Default")
      (node (ref "U2") (pin "A15") (pinfunction "IO_L51N_0_A15") (pintype "bidirectional"))
    )
    (net (code "185") (name "unconnected-(U2A-IO_L51P_0-PadC15)") (class "Default")
      (node (ref "U2") (pin "C15") (pinfunction "IO_L51P_0_C15") (pintype "bidirectional"))
    )
    (net (code "186") (name "unconnected-(U2A-IO_L62N_VREF_0-PadC16)") (class "Default")
      (node (ref "U2") (pin "C16") (pinfunction "IO_L62N_VREF_0_C16") (pintype "bidirectional"))
    )
    (net (code "187") (name "unconnected-(U2A-IO_L62P_0-PadD15)") (class "Default")
      (node (ref "U2") (pin "D15") (pinfunction "IO_L62P_0_D15") (pintype "bidirectional"))
    )
    (net (code "188") (name "unconnected-(U2A-IO_L63N_SCP6_0-PadA16)") (class "Default")
      (node (ref "U2") (pin "A16") (pinfunction "IO_L63N_SCP6_0_A16") (pintype "bidirectional"))
    )
    (net (code "189") (name "unconnected-(U2A-IO_L63P_SCP7_0-PadB16)") (class "Default")
      (node (ref "U2") (pin "B16") (pinfunction "IO_L63P_SCP7_0_B16") (pintype "bidirectional"))
    )
    (net (code "190") (name "unconnected-(U2A-IO_L64N_SCP4_0-PadA17)") (class "Default")
      (node (ref "U2") (pin "A17") (pinfunction "IO_L64N_SCP4_0_A17") (pintype "bidirectional"))
    )
    (net (code "191") (name "unconnected-(U2A-IO_L64P_SCP5_0-PadC17)") (class "Default")
      (node (ref "U2") (pin "C17") (pinfunction "IO_L64P_SCP5_0_C17") (pintype "bidirectional"))
    )
    (net (code "192") (name "unconnected-(U2A-IO_L65N_SCP2_0-PadA18)") (class "Default")
      (node (ref "U2") (pin "A18") (pinfunction "IO_L65N_SCP2_0_A18") (pintype "bidirectional"))
    )
    (net (code "193") (name "unconnected-(U2A-IO_L65P_SCP3_0-PadB18)") (class "Default")
      (node (ref "U2") (pin "B18") (pinfunction "IO_L65P_SCP3_0_B18") (pintype "bidirectional"))
    )
    (net (code "194") (name "unconnected-(U2A-IO_L66N_SCP0_0-PadD17)") (class "Default")
      (node (ref "U2") (pin "D17") (pinfunction "IO_L66N_SCP0_0_D17") (pintype "bidirectional"))
    )
    (net (code "195") (name "unconnected-(U2A-IO_L66P_SCP1_0-PadE16)") (class "Default")
      (node (ref "U2") (pin "E16") (pinfunction "IO_L66P_SCP1_0_E16") (pintype "bidirectional"))
    )
    (net (code "196") (name "unconnected-(U2B-IO_L47N_LDC_M1DQ1_1-PadN22)") (class "Default")
      (node (ref "U2") (pin "N22") (pinfunction "IO_L47N_LDC_M1DQ1_1_N22") (pintype "bidirectional+no_connect"))
    )
    (net (code "197") (name "unconnected-(U2B-IO_L48P_HDC_M1DQ8_1-PadP21)") (class "Default")
      (node (ref "U2") (pin "P21") (pinfunction "IO_L48P_HDC_M1DQ8_1_P21") (pintype "bidirectional+no_connect"))
    )
    (net (code "198") (name "unconnected-(U2B-IO_L58N_1-PadL15)") (class "Default")
      (node (ref "U2") (pin "L15") (pinfunction "IO_L58N_1_L15") (pintype "bidirectional"))
    )
    (net (code "199") (name "unconnected-(U2B-IO_L59N_1-PadP20)") (class "Default")
      (node (ref "U2") (pin "P20") (pinfunction "IO_L59N_1_P20") (pintype "bidirectional"))
    )
    (net (code "200") (name "unconnected-(U2B-IO_L59P_1-PadP19)") (class "Default")
      (node (ref "U2") (pin "P19") (pinfunction "IO_L59P_1_P19") (pintype "bidirectional"))
    )
    (net (code "201") (name "unconnected-(U2B-IO_L60N_1-PadW22)") (class "Default")
      (node (ref "U2") (pin "W22") (pinfunction "IO_L60N_1_W22") (pintype "bidirectional"))
    )
    (net (code "202") (name "unconnected-(U2B-IO_L60P_1-PadW20)") (class "Default")
      (node (ref "U2") (pin "W20") (pinfunction "IO_L60P_1_W20") (pintype "bidirectional"))
    )
    (net (code "203") (name "unconnected-(U2B-IO_L61N_1-PadK18)") (class "Default")
      (node (ref "U2") (pin "K18") (pinfunction "IO_L61N_1_K18") (pintype "bidirectional"))
    )
    (net (code "204") (name "unconnected-(U2B-IO_L61P_1-PadL17)") (class "Default")
      (node (ref "U2") (pin "L17") (pinfunction "IO_L61P_1_L17") (pintype "bidirectional"))
    )
    (net (code "205") (name "unconnected-(U2B-IO_L70N_1-PadV20)") (class "Default")
      (node (ref "U2") (pin "V20") (pinfunction "IO_L70N_1_V20") (pintype "bidirectional"))
    )
    (net (code "206") (name "unconnected-(U2B-IO_L70P_1-PadU19)") (class "Default")
      (node (ref "U2") (pin "U19") (pinfunction "IO_L70P_1_U19") (pintype "bidirectional"))
    )
    (net (code "207") (name "unconnected-(U2B-IO_L71N_1-PadM18)") (class "Default")
      (node (ref "U2") (pin "M18") (pinfunction "IO_L71N_1_M18") (pintype "bidirectional"))
    )
    (net (code "208") (name "unconnected-(U2B-IO_L71P_1-PadM17)") (class "Default")
      (node (ref "U2") (pin "M17") (pinfunction "IO_L71P_1_M17") (pintype "bidirectional"))
    )
    (net (code "209") (name "unconnected-(U2B-IO_L72N_1-PadN16)") (class "Default")
      (node (ref "U2") (pin "N16") (pinfunction "IO_L72N_1_N16") (pintype "bidirectional"))
    )
    (net (code "210") (name "unconnected-(U2B-IO_L72P_1-PadP17)") (class "Default")
      (node (ref "U2") (pin "P17") (pinfunction "IO_L72P_1_P17") (pintype "bidirectional"))
    )
    (net (code "211") (name "unconnected-(U2B-IO_L73N_1-PadR19)") (class "Default")
      (node (ref "U2") (pin "R19") (pinfunction "IO_L73N_1_R19") (pintype "bidirectional"))
    )
    (net (code "212") (name "unconnected-(U2B-IO_L73P_1-PadP18)") (class "Default")
      (node (ref "U2") (pin "P18") (pinfunction "IO_L73P_1_P18") (pintype "bidirectional"))
    )
    (net (code "213") (name "unconnected-(U2B-IO_L74N_DOUT_BUSY_1-PadT20)") (class "Default")
      (node (ref "U2") (pin "T20") (pinfunction "IO_L74N_DOUT_BUSY_1_T20") (pintype "bidirectional+no_connect"))
    )
    (net (code "214") (name "unconnected-(U2B-IO_L74P_AWAKE_1-PadT19)") (class "Default")
      (node (ref "U2") (pin "T19") (pinfunction "IO_L74P_AWAKE_1_T19") (pintype "bidirectional"))
    )
    (net (code "215") (name "unconnected-(U2C-IO_L2N_CMPMOSI_2-PadAB21)") (class "Default")
      (node (ref "U2") (pin "AB21") (pinfunction "IO_L2N_CMPMOSI_2_AB21") (pintype "bidirectional"))
    )
    (net (code "216") (name "unconnected-(U2C-IO_L2P_CMPCLK_2-PadAA21)") (class "Default")
      (node (ref "U2") (pin "AA21") (pinfunction "IO_L2P_CMPCLK_2_AA21") (pintype "bidirectional"))
    )
    (net (code "217") (name "unconnected-(U2C-IO_L4N_VREF_2-PadT17)") (class "Default")
      (node (ref "U2") (pin "T17") (pinfunction "IO_L4N_VREF_2_T17") (pintype "bidirectional"))
    )
    (net (code "218") (name "unconnected-(U2C-IO_L4P_2-PadT18)") (class "Default")
      (node (ref "U2") (pin "T18") (pinfunction "IO_L4P_2_T18") (pintype "bidirectional"))
    )
    (net (code "219") (name "unconnected-(U2C-IO_L5N_2-PadAB19)") (class "Default")
      (node (ref "U2") (pin "AB19") (pinfunction "IO_L5N_2_AB19") (pintype "bidirectional"))
    )
    (net (code "220") (name "unconnected-(U2C-IO_L5P_2-PadY19)") (class "Default")
      (node (ref "U2") (pin "Y19") (pinfunction "IO_L5P_2_Y19") (pintype "bidirectional"))
    )
    (net (code "221") (name "unconnected-(U2C-IO_L12N_D2_MISO3_2-PadU13)") (class "Default")
      (node (ref "U2") (pin "U13") (pinfunction "IO_L12N_D2_MISO3_2_U13") (pintype "bidirectional"))
    )
    (net (code "222") (name "unconnected-(U2C-IO_L12P_D1_MISO2_2-PadU14)") (class "Default")
      (node (ref "U2") (pin "U14") (pinfunction "IO_L12P_D1_MISO2_2_U14") (pintype "bidirectional"))
    )
    (net (code "223") (name "unconnected-(U2C-IO_L15N_2-PadAB17)") (class "Default")
      (node (ref "U2") (pin "AB17") (pinfunction "IO_L15N_2_AB17") (pintype "bidirectional"))
    )
    (net (code "224") (name "unconnected-(U2C-IO_L15P_2-PadY17)") (class "Default")
      (node (ref "U2") (pin "Y17") (pinfunction "IO_L15P_2_Y17") (pintype "bidirectional"))
    )
    (net (code "225") (name "unconnected-(U2C-IO_L19P_2-PadAA16)") (class "Default")
      (node (ref "U2") (pin "AA16") (pinfunction "IO_L19P_2_AA16") (pintype "bidirectional"))
    )
    (net (code "226") (name "unconnected-(U2C-IO_L21N_2-PadAB15)") (class "Default")
      (node (ref "U2") (pin "AB15") (pinfunction "IO_L21N_2_AB15") (pintype "bidirectional"))
    )
    (net (code "227") (name "unconnected-(U2C-IO_L30N_GCLK0_USERCCLK_2-PadAB13)") (class "Default")
      (node (ref "U2") (pin "AB13") (pinfunction "IO_L30N_GCLK0_USERCCLK_2_AB13") (pintype "bidirectional"))
    )
    (net (code "228") (name "unconnected-(U2C-IO_L32P_GCLK29_2-PadY11)") (class "Default")
      (node (ref "U2") (pin "Y11") (pinfunction "IO_L32P_GCLK29_2_Y11") (pintype "bidirectional"))
    )
    (net (code "229") (name "unconnected-(U2C-IO_L42N_2-PadW11)") (class "Default")
      (node (ref "U2") (pin "W11") (pinfunction "IO_L42N_2_W11") (pintype "bidirectional"))
    )
    (net (code "230") (name "unconnected-(U2C-IO_L42P_2-PadV11)") (class "Default")
      (node (ref "U2") (pin "V11") (pinfunction "IO_L42P_2_V11") (pintype "bidirectional"))
    )
    (net (code "231") (name "unconnected-(U2C-IO_L43N_2-PadAB9)") (class "Default")
      (node (ref "U2") (pin "AB9") (pinfunction "IO_L43N_2_AB9") (pintype "bidirectional"))
    )
    (net (code "232") (name "unconnected-(U2C-IO_L43P_2-PadY9)") (class "Default")
      (node (ref "U2") (pin "Y9") (pinfunction "IO_L43P_2_Y9") (pintype "bidirectional"))
    )
    (net (code "233") (name "unconnected-(U2C-IO_L48N_RDWR_B_VREF_2-PadAB7)") (class "Default")
      (node (ref "U2") (pin "AB7") (pinfunction "IO_L48N_RDWR_B_VREF_2_AB7") (pintype "bidirectional"))
    )
    (net (code "234") (name "unconnected-(U2C-IO_L48P_D7_2-PadY7)") (class "Default")
      (node (ref "U2") (pin "Y7") (pinfunction "IO_L48P_D7_2_Y7") (pintype "bidirectional"))
    )
    (net (code "235") (name "unconnected-(U2C-IO_L49N_D4_2-PadAB6)") (class "Default")
      (node (ref "U2") (pin "AB6") (pinfunction "IO_L49N_D4_2_AB6") (pintype "bidirectional"))
    )
    (net (code "236") (name "unconnected-(U2C-IO_L49P_D3_2-PadAA6)") (class "Default")
      (node (ref "U2") (pin "AA6") (pinfunction "IO_L49P_D3_2_AA6") (pintype "bidirectional"))
    )
    (net (code "237") (name "unconnected-(U2C-IO_L57N_2-PadAB4)") (class "Default")
      (node (ref "U2") (pin "AB4") (pinfunction "IO_L57N_2_AB4") (pintype "bidirectional"))
    )
    (net (code "238") (name "unconnected-(U2C-IO_L57P_2-PadAA4)") (class "Default")
      (node (ref "U2") (pin "AA4") (pinfunction "IO_L57P_2_AA4") (pintype "bidirectional"))
    )
    (net (code "239") (name "unconnected-(U2C-IO_L62N_D6_2-PadY4)") (class "Default")
      (node (ref "U2") (pin "Y4") (pinfunction "IO_L62N_D6_2_Y4") (pintype "bidirectional"))
    )
    (net (code "240") (name "unconnected-(U2C-IO_L62P_D5_2-PadW4)") (class "Default")
      (node (ref "U2") (pin "W4") (pinfunction "IO_L62P_D5_2_W4") (pintype "bidirectional"))
    )
    (net (code "241") (name "unconnected-(U2C-IO_L64N_D9_2-PadAB2)") (class "Default")
      (node (ref "U2") (pin "AB2") (pinfunction "IO_L64N_D9_2_AB2") (pintype "bidirectional"))
    )
    (net (code "242") (name "unconnected-(U2C-IO_L64P_D8_2-PadAA2)") (class "Default")
      (node (ref "U2") (pin "AA2") (pinfunction "IO_L64P_D8_2_AA2") (pintype "bidirectional"))
    )
    (net (code "243") (name "unconnected-(U2D-IO_L7N_3-PadP7)") (class "Default")
      (node (ref "U2") (pin "P7") (pinfunction "IO_L7N_3_P7") (pintype "bidirectional"))
    )
    (net (code "244") (name "unconnected-(U2D-IO_L7P_3-PadP8)") (class "Default")
      (node (ref "U2") (pin "P8") (pinfunction "IO_L7P_3_P8") (pintype "bidirectional"))
    )
    (net (code "245") (name "unconnected-(U2D-IO_L32N_M3DQ15_3-PadV1)") (class "Default")
      (node (ref "U2") (pin "V1") (pinfunction "IO_L32N_M3DQ15_3_V1") (pintype "bidirectional"))
    )
    (net (code "246") (name "unconnected-(U2D-IO_L41N_GCLK26_M3DQ5_3-PadJ1)") (class "Default")
      (node (ref "U2") (pin "J1") (pinfunction "IO_L41N_GCLK26_M3DQ5_3_J1") (pintype "bidirectional"))
    )
    (net (code "247") (name "unconnected-(U2D-IO_L42N_GCLK24_M3LDM_3-PadL4)") (class "Default")
      (node (ref "U2") (pin "L4") (pinfunction "IO_L42N_GCLK24_M3LDM_3_L4") (pintype "bidirectional"))
    )
    (net (code "248") (name "unconnected-(U2D-IO_L42P_GCLK25_TRDY2_M3UDM_3-PadM3)") (class "Default")
      (node (ref "U2") (pin "M3") (pinfunction "IO_L42P_GCLK25_TRDY2_M3UDM_3_M3") (pintype "bidirectional"))
    )
    (net (code "249") (name "unconnected-(U2D-IO_L43N_GCLK22_IRDY2_M3CASN_3-PadK4)") (class "Default")
      (node (ref "U2") (pin "K4") (pinfunction "IO_L43N_GCLK22_IRDY2_M3CASN_3_K4") (pintype "bidirectional"))
    )
    (net (code "250") (name "unconnected-(U2D-IO_L43P_GCLK23_M3RASN_3-PadK5)") (class "Default")
      (node (ref "U2") (pin "K5") (pinfunction "IO_L43P_GCLK23_M3RASN_3_K5") (pintype "bidirectional"))
    )
    (net (code "251") (name "unconnected-(U2D-IO_L44N_GCLK20_M3A6_3-PadJ4)") (class "Default")
      (node (ref "U2") (pin "J4") (pinfunction "IO_L44N_GCLK20_M3A6_3_J4") (pintype "bidirectional"))
    )
    (net (code "252") (name "unconnected-(U2D-IO_L44P_GCLK21_M3A5_3-PadK3)") (class "Default")
      (node (ref "U2") (pin "K3") (pinfunction "IO_L44P_GCLK21_M3A5_3_K3") (pintype "bidirectional"))
    )
    (net (code "253") (name "unconnected-(U2D-IO_L45N_M3ODT_3-PadJ6)") (class "Default")
      (node (ref "U2") (pin "J6") (pinfunction "IO_L45N_M3ODT_3_J6") (pintype "bidirectional"))
    )
    (net (code "254") (name "unconnected-(U2D-IO_L45P_M3A3_3-PadK6)") (class "Default")
      (node (ref "U2") (pin "K6") (pinfunction "IO_L45P_M3A3_3_K6") (pintype "bidirectional"))
    )
    (net (code "255") (name "unconnected-(U2D-IO_L46N_M3CLKN_3-PadH3)") (class "Default")
      (node (ref "U2") (pin "H3") (pinfunction "IO_L46N_M3CLKN_3_H3") (pintype "bidirectional"))
    )
    (net (code "256") (name "unconnected-(U2D-IO_L46P_M3CLK_3-PadH4)") (class "Default")
      (node (ref "U2") (pin "H4") (pinfunction "IO_L46P_M3CLK_3_H4") (pintype "bidirectional"))
    )
    (net (code "257") (name "unconnected-(U2D-IO_L47N_M3A1_3-PadH1)") (class "Default")
      (node (ref "U2") (pin "H1") (pinfunction "IO_L47N_M3A1_3_H1") (pintype "bidirectional"))
    )
    (net (code "258") (name "unconnected-(U2D-IO_L47P_M3A0_3-PadH2)") (class "Default")
      (node (ref "U2") (pin "H2") (pinfunction "IO_L47P_M3A0_3_H2") (pintype "bidirectional"))
    )
    (net (code "259") (name "unconnected-(U2D-IO_L48N_M3BA1_3-PadG1)") (class "Default")
      (node (ref "U2") (pin "G1") (pinfunction "IO_L48N_M3BA1_3_G1") (pintype "bidirectional"))
    )
    (net (code "260") (name "unconnected-(U2D-IO_L48P_M3BA0_3-PadG3)") (class "Default")
      (node (ref "U2") (pin "G3") (pinfunction "IO_L48P_M3BA0_3_G3") (pintype "bidirectional"))
    )
    (net (code "261") (name "unconnected-(U2D-IO_L49N_M3A2_3-PadH5)") (class "Default")
      (node (ref "U2") (pin "H5") (pinfunction "IO_L49N_M3A2_3_H5") (pintype "bidirectional"))
    )
    (net (code "262") (name "unconnected-(U2D-IO_L49P_M3A7_3-PadH6)") (class "Default")
      (node (ref "U2") (pin "H6") (pinfunction "IO_L49P_M3A7_3_H6") (pintype "bidirectional"))
    )
    (net (code "263") (name "unconnected-(U2D-IO_L50N_M3BA2_3-PadF1)") (class "Default")
      (node (ref "U2") (pin "F1") (pinfunction "IO_L50N_M3BA2_3_F1") (pintype "bidirectional"))
    )
    (net (code "264") (name "unconnected-(U2D-IO_L50P_M3WE_3-PadF2)") (class "Default")
      (node (ref "U2") (pin "F2") (pinfunction "IO_L50P_M3WE_3_F2") (pintype "bidirectional"))
    )
    (net (code "265") (name "unconnected-(U2D-IO_L51N_M3A4_3-PadF3)") (class "Default")
      (node (ref "U2") (pin "F3") (pinfunction "IO_L51N_M3A4_3_F3") (pintype "bidirectional"))
    )
    (net (code "266") (name "unconnected-(U2D-IO_L51P_M3A10_3-PadG4)") (class "Default")
      (node (ref "U2") (pin "G4") (pinfunction "IO_L51P_M3A10_3_G4") (pintype "bidirectional"))
    )
    (net (code "267") (name "unconnected-(U2D-IO_L52N_M3A9_3-PadE1)") (class "Default")
      (node (ref "U2") (pin "E1") (pinfunction "IO_L52N_M3A9_3_E1") (pintype "bidirectional"))
    )
    (net (code "268") (name "unconnected-(U2D-IO_L52P_M3A8_3-PadE3)") (class "Default")
      (node (ref "U2") (pin "E3") (pinfunction "IO_L52P_M3A8_3_E3") (pintype "bidirectional"))
    )
    (net (code "269") (name "unconnected-(U2D-IO_L53N_M3A12_3-PadD1)") (class "Default")
      (node (ref "U2") (pin "D1") (pinfunction "IO_L53N_M3A12_3_D1") (pintype "bidirectional"))
    )
    (net (code "270") (name "unconnected-(U2D-IO_L53P_M3CKE_3-PadD2)") (class "Default")
      (node (ref "U2") (pin "D2") (pinfunction "IO_L53P_M3CKE_3_D2") (pintype "bidirectional"))
    )
    (net (code "271") (name "unconnected-(U2D-IO_L54N_M3A11_3-PadC1)") (class "Default")
      (node (ref "U2") (pin "C1") (pinfunction "IO_L54N_M3A11_3_C1") (pintype "bidirectional"))
    )
    (net (code "272") (name "unconnected-(U2D-IO_L54P_M3RESET_3-PadC3)") (class "Default")
      (node (ref "U2") (pin "C3") (pinfunction "IO_L54P_M3RESET_3_C3") (pintype "bidirectional"))
    )
    (net (code "273") (name "unconnected-(U2D-IO_L55N_M3A14_3-PadF5)") (class "Default")
      (node (ref "U2") (pin "F5") (pinfunction "IO_L55N_M3A14_3_F5") (pintype "bidirectional"))
    )
    (net (code "274") (name "unconnected-(U2D-IO_L55P_M3A13_3-PadG6)") (class "Default")
      (node (ref "U2") (pin "G6") (pinfunction "IO_L55P_M3A13_3_G6") (pintype "bidirectional"))
    )
    (net (code "275") (name "unconnected-(U2D-IO_L57N_VREF_3-PadK8)") (class "Default")
      (node (ref "U2") (pin "K8") (pinfunction "IO_L57N_VREF_3_K8") (pintype "bidirectional"))
    )
    (net (code "276") (name "unconnected-(U2D-IO_L57P_3-PadK7)") (class "Default")
      (node (ref "U2") (pin "K7") (pinfunction "IO_L57P_3_K7") (pintype "bidirectional"))
    )
    (net (code "277") (name "unconnected-(U2D-IO_L58N_3-PadE4)") (class "Default")
      (node (ref "U2") (pin "E4") (pinfunction "IO_L58N_3_E4") (pintype "bidirectional"))
    )
    (net (code "278") (name "unconnected-(U2D-IO_L58P_3-PadD5)") (class "Default")
      (node (ref "U2") (pin "D5") (pinfunction "IO_L58P_3_D5") (pintype "bidirectional"))
    )
    (net (code "279") (name "unconnected-(U2D-IO_L59N_3-PadH8)") (class "Default")
      (node (ref "U2") (pin "H8") (pinfunction "IO_L59N_3_H8") (pintype "bidirectional"))
    )
    (net (code "280") (name "unconnected-(U2D-IO_L80N_3-PadF7)") (class "Default")
      (node (ref "U2") (pin "F7") (pinfunction "IO_L80N_3_F7") (pintype "bidirectional"))
    )
    (net (code "281") (name "unconnected-(U2D-IO_L81N_3-PadC4)") (class "Default")
      (node (ref "U2") (pin "C4") (pinfunction "IO_L81N_3_C4") (pintype "bidirectional"))
    )
    (net (code "282") (name "unconnected-(U2D-IO_L81P_3-PadD3)") (class "Default")
      (node (ref "U2") (pin "D3") (pinfunction "IO_L81P_3_D3") (pintype "bidirectional"))
    )
  )
)
